# layout2.net
KiCad netlist of a schematic drawn in EAGLE
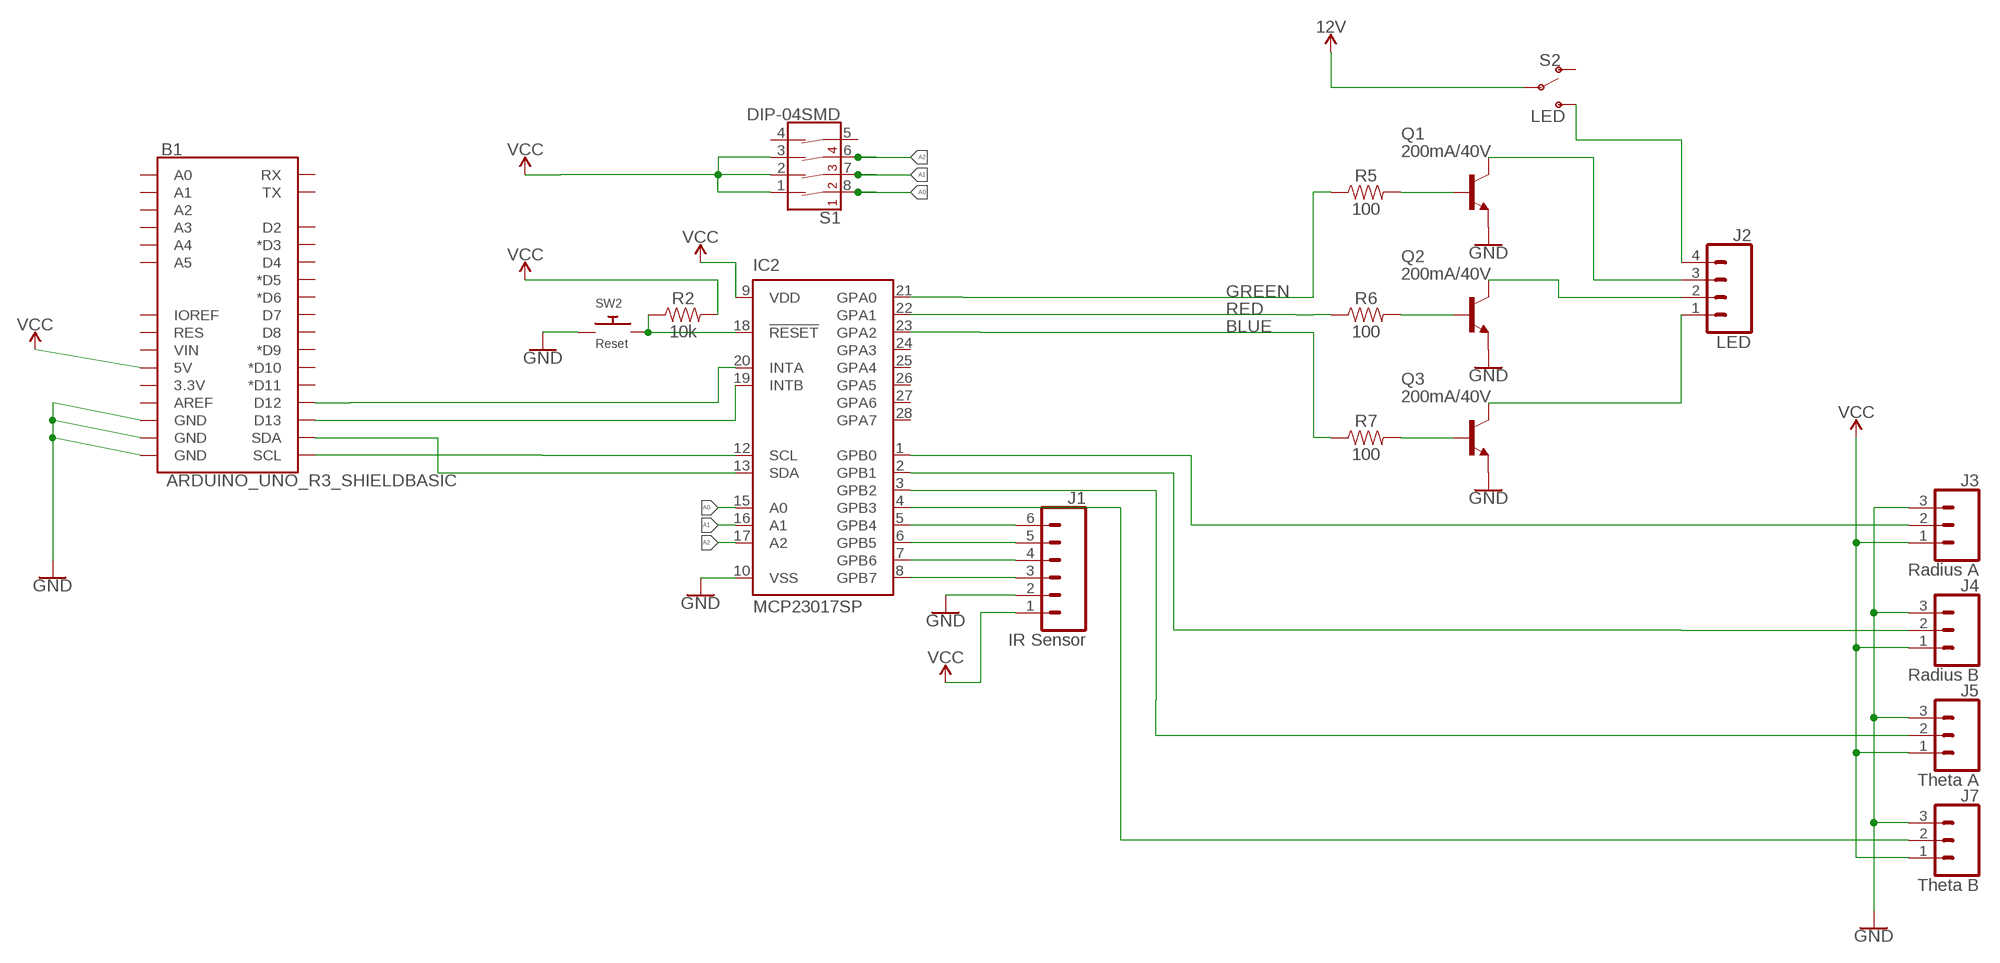
[diagram p0: schematic, sheet 1]

(export (version "E")
  (design (tool "Eeschema 10.0.6"))
  (components
    (comp (ref "B1")
      (value "ARDUINO_UNO_R3_SHIELDBASIC")
      (footprint "eagle-import:UNO_R3_SHIELD")
      (libsource (lib "eagle-import") (part "ARDUINO_UNO_R3_SHIELDBASIC"))
    )
    (comp (ref "IC2")
      (value "MCP23017SP")
      (footprint "eagle-import:DIL28-3")
      (libsource (lib "eagle-import") (part "MCP23017SP"))
    )
    (comp (ref "J1")
      (value "IR Sensor")
      (footprint "eagle-import:1X06")
      (libsource (lib "eagle-import") (part "CONN_06SILK_FEMALE_PTH"))
    )
    (comp (ref "J2")
      (value "LED")
      (footprint "eagle-import:MOLEX-1X4")
      (libsource (lib "eagle-import") (part "CONN_04POLAR"))
    )
    (comp (ref "J3")
      (value "Radius A")
      (footprint "eagle-import:MOLEX-1X3")
      (libsource (lib "eagle-import") (part "CONN_03POLAR"))
    )
    (comp (ref "J4")
      (value "Radius B")
      (footprint "eagle-import:MOLEX-1X3")
      (libsource (lib "eagle-import") (part "CONN_03POLAR"))
    )
    (comp (ref "J5")
      (value "Theta A")
      (footprint "eagle-import:MOLEX-1X3")
      (libsource (lib "eagle-import") (part "CONN_03POLAR"))
    )
    (comp (ref "J7")
      (value "Theta B")
      (footprint "eagle-import:MOLEX-1X3")
      (libsource (lib "eagle-import") (part "CONN_03POLAR"))
    )
    (comp (ref "Q1")
      (value "200mA/40V")
      (footprint "eagle-import:TO220")
      (libsource (lib "eagle-import") (part "-NPN-TO220"))
    )
    (comp (ref "Q2")
      (value "200mA/40V")
      (footprint "eagle-import:TO220")
      (libsource (lib "eagle-import") (part "-NPN-TO220"))
    )
    (comp (ref "Q3")
      (value "200mA/40V")
      (footprint "eagle-import:TO220")
      (libsource (lib "eagle-import") (part "-NPN-TO220"))
    )
    (comp (ref "R2")
      (value "10k")
      (footprint "eagle-import:0603")
      (libsource (lib "eagle-import") (part "10KOHM-0603-1/10W-1%"))
    )
    (comp (ref "R5")
      (value "100")
      (footprint "eagle-import:0603")
      (libsource (lib "eagle-import") (part "100OHM-0603-1/4W-5%"))
    )
    (comp (ref "R6")
      (value "100")
      (footprint "eagle-import:0603")
      (libsource (lib "eagle-import") (part "100OHM-0603-1/4W-5%"))
    )
    (comp (ref "R7")
      (value "100")
      (footprint "eagle-import:0603")
      (libsource (lib "eagle-import") (part "100OHM-0603-1/4W-5%"))
    )
    (comp (ref "S1")
      (value "DIP-04SMD")
      (footprint "eagle-import:DIPSWITCH-04-SMD")
      (libsource (lib "eagle-import") (part "DIP-04SMD"))
    )
    (comp (ref "S2")
      (value "LED")
      (footprint "eagle-import:SWITCH_SPDT_PTH_11.6X4.0MM")
      (libsource (lib "eagle-import") (part "SWITCH-SPDT-PTH-11.6X4.0MM"))
    )
    (comp (ref "SW2")
      (value "Reset")
      (footprint "eagle-import:BTN_CK_KSS")
      (libsource (lib "eagle-import") (part "SWITCH_PUSHBUTTONC&K_KSS"))
    )
  )
  (nets
    (net (code "1") (name "/BLUE") (class "Default")
      (node (ref "IC2") (pin "23") (pinfunction "GPA2_23") (pintype "bidirectional"))
      (node (ref "R7") (pin "1") (pinfunction "1_1") (pintype "passive"))
    )
    (net (code "2") (name "/GREEN") (class "Default")
      (node (ref "IC2") (pin "21") (pinfunction "GPA0_21") (pintype "bidirectional"))
      (node (ref "R5") (pin "1") (pinfunction "1_1") (pintype "passive"))
    )
    (net (code "3") (name "/RED") (class "Default")
      (node (ref "IC2") (pin "22") (pinfunction "GPA1_22") (pintype "bidirectional"))
      (node (ref "R6") (pin "1") (pinfunction "1_1") (pintype "passive"))
    )
    (net (code "4") (name "12V") (class "Default")
      (node (ref "S2") (pin "2") (pinfunction "P_2") (pintype "passive"))
    )
    (net (code "5") (name "A0") (class "Default")
      (node (ref "IC2") (pin "15") (pinfunction "A0_15") (pintype "input"))
      (node (ref "S1") (pin "8") (pinfunction "1B_8") (pintype "bidirectional"))
    )
    (net (code "6") (name "A1") (class "Default")
      (node (ref "IC2") (pin "16") (pinfunction "A1_16") (pintype "input"))
      (node (ref "S1") (pin "7") (pinfunction "2B_7") (pintype "bidirectional"))
    )
    (net (code "7") (name "A2") (class "Default")
      (node (ref "IC2") (pin "17") (pinfunction "A2_17") (pintype "input"))
      (node (ref "S1") (pin "6") (pinfunction "3B_6") (pintype "bidirectional"))
    )
    (net (code "8") (name "GND") (class "Default")
      (node (ref "B1") (pin "GND@0") (pinfunction "GND_GND@0") (pintype "bidirectional"))
      (node (ref "B1") (pin "GND@1") (pinfunction "GND_GND@1") (pintype "bidirectional"))
      (node (ref "B1") (pin "GND@2") (pinfunction "GND_GND@2") (pintype "bidirectional"))
      (node (ref "IC2") (pin "10") (pinfunction "VSS_10") (pintype "power_in"))
      (node (ref "J1") (pin "2") (pinfunction "2_2") (pintype "passive"))
      (node (ref "J3") (pin "3") (pinfunction "3_3") (pintype "passive"))
      (node (ref "J4") (pin "3") (pinfunction "3_3") (pintype "passive"))
      (node (ref "J5") (pin "3") (pinfunction "3_3") (pintype "passive"))
      (node (ref "J7") (pin "3") (pinfunction "3_3") (pintype "passive"))
      (node (ref "Q1") (pin "3") (pinfunction "E_3") (pintype "passive"))
      (node (ref "Q2") (pin "3") (pinfunction "E_3") (pintype "passive"))
      (node (ref "Q3") (pin "3") (pinfunction "E_3") (pintype "passive"))
      (node (ref "SW2") (pin "P$1") (pinfunction "P$1_P$1") (pintype "passive"))
    )
    (net (code "9") (name "Net-(IC2-GPB0)") (class "Default")
      (node (ref "IC2") (pin "1") (pinfunction "GPB0_1") (pintype "bidirectional"))
      (node (ref "J3") (pin "2") (pinfunction "2_2") (pintype "passive"))
    )
    (net (code "10") (name "Net-(IC2-GPB1)") (class "Default")
      (node (ref "IC2") (pin "2") (pinfunction "GPB1_2") (pintype "bidirectional"))
      (node (ref "J4") (pin "2") (pinfunction "2_2") (pintype "passive"))
    )
    (net (code "11") (name "Net-(IC2-GPB2)") (class "Default")
      (node (ref "IC2") (pin "3") (pinfunction "GPB2_3") (pintype "bidirectional"))
      (node (ref "J5") (pin "2") (pinfunction "2_2") (pintype "passive"))
    )
    (net (code "12") (name "Net-(IC2-GPB3)") (class "Default")
      (node (ref "IC2") (pin "4") (pinfunction "GPB3_4") (pintype "bidirectional"))
      (node (ref "J7") (pin "2") (pinfunction "2_2") (pintype "passive"))
    )
    (net (code "13") (name "Net-(IC2-GPB4)") (class "Default")
      (node (ref "IC2") (pin "5") (pinfunction "GPB4_5") (pintype "bidirectional"))
      (node (ref "J1") (pin "6") (pinfunction "6_6") (pintype "passive"))
    )
    (net (code "14") (name "Net-(IC2-GPB5)") (class "Default")
      (node (ref "IC2") (pin "6") (pinfunction "GPB5_6") (pintype "bidirectional"))
      (node (ref "J1") (pin "5") (pinfunction "5_5") (pintype "passive"))
    )
    (net (code "15") (name "Net-(IC2-GPB6)") (class "Default")
      (node (ref "IC2") (pin "7") (pinfunction "GPB6_7") (pintype "bidirectional"))
      (node (ref "J1") (pin "4") (pinfunction "4_4") (pintype "passive"))
    )
    (net (code "16") (name "Net-(IC2-GPB7)") (class "Default")
      (node (ref "IC2") (pin "8") (pinfunction "GPB7_8") (pintype "bidirectional"))
      (node (ref "J1") (pin "3") (pinfunction "3_3") (pintype "passive"))
    )
    (net (code "17") (name "Net-(IC2-INTA)") (class "Default")
      (node (ref "B1") (pin "D12") (pinfunction "D12_D12") (pintype "bidirectional"))
      (node (ref "IC2") (pin "20") (pinfunction "INTA_20") (pintype "output"))
    )
    (net (code "18") (name "Net-(IC2-INTB)") (class "Default")
      (node (ref "B1") (pin "D13") (pinfunction "D13_D13") (pintype "bidirectional"))
      (node (ref "IC2") (pin "19") (pinfunction "INTB_19") (pintype "output"))
    )
    (net (code "19") (name "Net-(IC2-SCL)") (class "Default")
      (node (ref "B1") (pin "SCL") (pinfunction "SCL_SCL") (pintype "bidirectional"))
      (node (ref "IC2") (pin "12") (pinfunction "SCL_12") (pintype "input"))
    )
    (net (code "20") (name "Net-(IC2-SDA)") (class "Default")
      (node (ref "B1") (pin "SDA") (pinfunction "SDA_SDA") (pintype "bidirectional"))
      (node (ref "IC2") (pin "13") (pinfunction "SDA_13") (pintype "bidirectional"))
    )
    (net (code "21") (name "Net-(IC2-~{RESET})") (class "Default")
      (node (ref "IC2") (pin "18") (pinfunction "~{RESET}_18") (pintype "input"))
      (node (ref "R2") (pin "1") (pinfunction "1_1") (pintype "passive"))
      (node (ref "SW2") (pin "P$2") (pinfunction "P$2_P$2") (pintype "passive"))
    )
    (net (code "22") (name "Net-(Q1-B)") (class "Default")
      (node (ref "Q1") (pin "1") (pinfunction "B_1") (pintype "passive"))
      (node (ref "R5") (pin "2") (pinfunction "2_2") (pintype "passive"))
    )
    (net (code "23") (name "Net-(Q1-C)") (class "Default")
      (node (ref "J2") (pin "3") (pinfunction "3_3") (pintype "passive"))
      (node (ref "Q1") (pin "2") (pinfunction "C_2") (pintype "passive"))
    )
    (net (code "24") (name "Net-(Q2-B)") (class "Default")
      (node (ref "Q2") (pin "1") (pinfunction "B_1") (pintype "passive"))
      (node (ref "R6") (pin "2") (pinfunction "2_2") (pintype "passive"))
    )
    (net (code "25") (name "Net-(Q2-C)") (class "Default")
      (node (ref "J2") (pin "2") (pinfunction "2_2") (pintype "passive"))
      (node (ref "Q2") (pin "2") (pinfunction "C_2") (pintype "passive"))
    )
    (net (code "26") (name "Net-(Q3-B)") (class "Default")
      (node (ref "Q3") (pin "1") (pinfunction "B_1") (pintype "passive"))
      (node (ref "R7") (pin "2") (pinfunction "2_2") (pintype "passive"))
    )
    (net (code "27") (name "Net-(Q3-C)") (class "Default")
      (node (ref "J2") (pin "1") (pinfunction "1_1") (pintype "passive"))
      (node (ref "Q3") (pin "2") (pinfunction "C_2") (pintype "passive"))
    )
    (net (code "28") (name "Net-(S2-S)") (class "Default")
      (node (ref "J2") (pin "4") (pinfunction "4_4") (pintype "passive"))
      (node (ref "S2") (pin "3") (pinfunction "S_3") (pintype "passive"))
    )
    (net (code "29") (name "VCC") (class "Default")
      (node (ref "B1") (pin "5V") (pinfunction "5V_5V") (pintype "bidirectional"))
      (node (ref "IC2") (pin "9") (pinfunction "VDD_9") (pintype "power_in"))
      (node (ref "J1") (pin "1") (pinfunction "1_1") (pintype "passive"))
      (node (ref "J3") (pin "1") (pinfunction "1_1") (pintype "passive"))
      (node (ref "J4") (pin "1") (pinfunction "1_1") (pintype "passive"))
      (node (ref "J5") (pin "1") (pinfunction "1_1") (pintype "passive"))
      (node (ref "J7") (pin "1") (pinfunction "1_1") (pintype "passive"))
      (node (ref "R2") (pin "2") (pinfunction "2_2") (pintype "passive"))
      (node (ref "S1") (pin "1") (pinfunction "1A_1") (pintype "bidirectional"))
      (node (ref "S1") (pin "2") (pinfunction "2A_2") (pintype "bidirectional"))
      (node (ref "S1") (pin "3") (pinfunction "3A_3") (pintype "bidirectional"))
    )
    (net (code "30") (name "unconnected-(B1-*D3-PadD3)") (class "Default")
      (node (ref "B1") (pin "D3") (pinfunction "*D3_D3") (pintype "bidirectional"))
    )
    (net (code "31") (name "unconnected-(B1-*D5-PadD5)") (class "Default")
      (node (ref "B1") (pin "D5") (pinfunction "*D5_D5") (pintype "bidirectional"))
    )
    (net (code "32") (name "unconnected-(B1-*D6-PadD6)") (class "Default")
      (node (ref "B1") (pin "D6") (pinfunction "*D6_D6") (pintype "bidirectional"))
    )
    (net (code "33") (name "unconnected-(B1-*D9-PadD9)") (class "Default")
      (node (ref "B1") (pin "D9") (pinfunction "*D9_D9") (pintype "bidirectional"))
    )
    (net (code "34") (name "unconnected-(B1-*D10-PadD10)") (class "Default")
      (node (ref "B1") (pin "D10") (pinfunction "*D10_D10") (pintype "bidirectional"))
    )
    (net (code "35") (name "unconnected-(B1-*D11-PadD11)") (class "Default")
      (node (ref "B1") (pin "D11") (pinfunction "*D11_D11") (pintype "bidirectional"))
    )
    (net (code "36") (name "unconnected-(B1-Pad3.3V)") (class "Default")
      (node (ref "B1") (pin "3.3V") (pinfunction "3.3V_3.3V") (pintype "bidirectional"))
    )
    (net (code "37") (name "unconnected-(B1-PadA0)") (class "Default")
      (node (ref "B1") (pin "A0") (pinfunction "A0_A0") (pintype "bidirectional"))
    )
    (net (code "38") (name "unconnected-(B1-PadA1)") (class "Default")
      (node (ref "B1") (pin "A1") (pinfunction "A1_A1") (pintype "bidirectional"))
    )
    (net (code "39") (name "unconnected-(B1-PadA2)") (class "Default")
      (node (ref "B1") (pin "A2") (pinfunction "A2_A2") (pintype "bidirectional"))
    )
    (net (code "40") (name "unconnected-(B1-PadA3)") (class "Default")
      (node (ref "B1") (pin "A3") (pinfunction "A3_A3") (pintype "bidirectional"))
    )
    (net (code "41") (name "unconnected-(B1-PadA4)") (class "Default")
      (node (ref "B1") (pin "A4") (pinfunction "A4_A4") (pintype "bidirectional"))
    )
    (net (code "42") (name "unconnected-(B1-PadA5)") (class "Default")
      (node (ref "B1") (pin "A5") (pinfunction "A5_A5") (pintype "bidirectional"))
    )
    (net (code "43") (name "unconnected-(B1-PadAREF)") (class "Default")
      (node (ref "B1") (pin "AREF") (pinfunction "AREF_AREF") (pintype "bidirectional"))
    )
    (net (code "44") (name "unconnected-(B1-PadD2)") (class "Default")
      (node (ref "B1") (pin "D2") (pinfunction "D2_D2") (pintype "bidirectional"))
    )
    (net (code "45") (name "unconnected-(B1-PadD4)") (class "Default")
      (node (ref "B1") (pin "D4") (pinfunction "D4_D4") (pintype "bidirectional"))
    )
    (net (code "46") (name "unconnected-(B1-PadD7)") (class "Default")
      (node (ref "B1") (pin "D7") (pinfunction "D7_D7") (pintype "bidirectional"))
    )
    (net (code "47") (name "unconnected-(B1-PadD8)") (class "Default")
      (node (ref "B1") (pin "D8") (pinfunction "D8_D8") (pintype "bidirectional"))
    )
    (net (code "48") (name "unconnected-(B1-PadIOREF)") (class "Default")
      (node (ref "B1") (pin "IOREF") (pinfunction "IOREF_IOREF") (pintype "bidirectional"))
    )
    (net (code "49") (name "unconnected-(B1-PadRES)") (class "Default")
      (node (ref "B1") (pin "RES") (pinfunction "RES_RES") (pintype "bidirectional"))
    )
    (net (code "50") (name "unconnected-(B1-PadRX)") (class "Default")
      (node (ref "B1") (pin "RX") (pinfunction "RX_RX") (pintype "bidirectional"))
    )
    (net (code "51") (name "unconnected-(B1-PadTX)") (class "Default")
      (node (ref "B1") (pin "TX") (pinfunction "TX_TX") (pintype "bidirectional"))
    )
    (net (code "52") (name "unconnected-(B1-PadVIN)") (class "Default")
      (node (ref "B1") (pin "VIN") (pinfunction "VIN_VIN") (pintype "bidirectional"))
    )
    (net (code "53") (name "unconnected-(IC2-GPA3-Pad24)") (class "Default")
      (node (ref "IC2") (pin "24") (pinfunction "GPA3_24") (pintype "bidirectional"))
    )
    (net (code "54") (name "unconnected-(IC2-GPA4-Pad25)") (class "Default")
      (node (ref "IC2") (pin "25") (pinfunction "GPA4_25") (pintype "bidirectional"))
    )
    (net (code "55") (name "unconnected-(IC2-GPA5-Pad26)") (class "Default")
      (node (ref "IC2") (pin "26") (pinfunction "GPA5_26") (pintype "bidirectional"))
    )
    (net (code "56") (name "unconnected-(IC2-GPA6-Pad27)") (class "Default")
      (node (ref "IC2") (pin "27") (pinfunction "GPA6_27") (pintype "bidirectional"))
    )
    (net (code "57") (name "unconnected-(IC2-GPA7-Pad28)") (class "Default")
      (node (ref "IC2") (pin "28") (pinfunction "GPA7_28") (pintype "bidirectional"))
    )
    (net (code "58") (name "unconnected-(S1-4A-Pad4)") (class "Default")
      (node (ref "S1") (pin "4") (pinfunction "4A_4") (pintype "bidirectional"))
    )
    (net (code "59") (name "unconnected-(S1-4B-Pad5)") (class "Default")
      (node (ref "S1") (pin "5") (pinfunction "4B_5") (pintype "bidirectional"))
    )
    (net (code "60") (name "unconnected-(S2-O-Pad1)") (class "Default")
      (node (ref "S2") (pin "1") (pinfunction "O_1") (pintype "passive"))
    )
  )
)
